# Universal_Board_Side_Mount.net
KiCad netlist of a schematic drawn in EAGLE
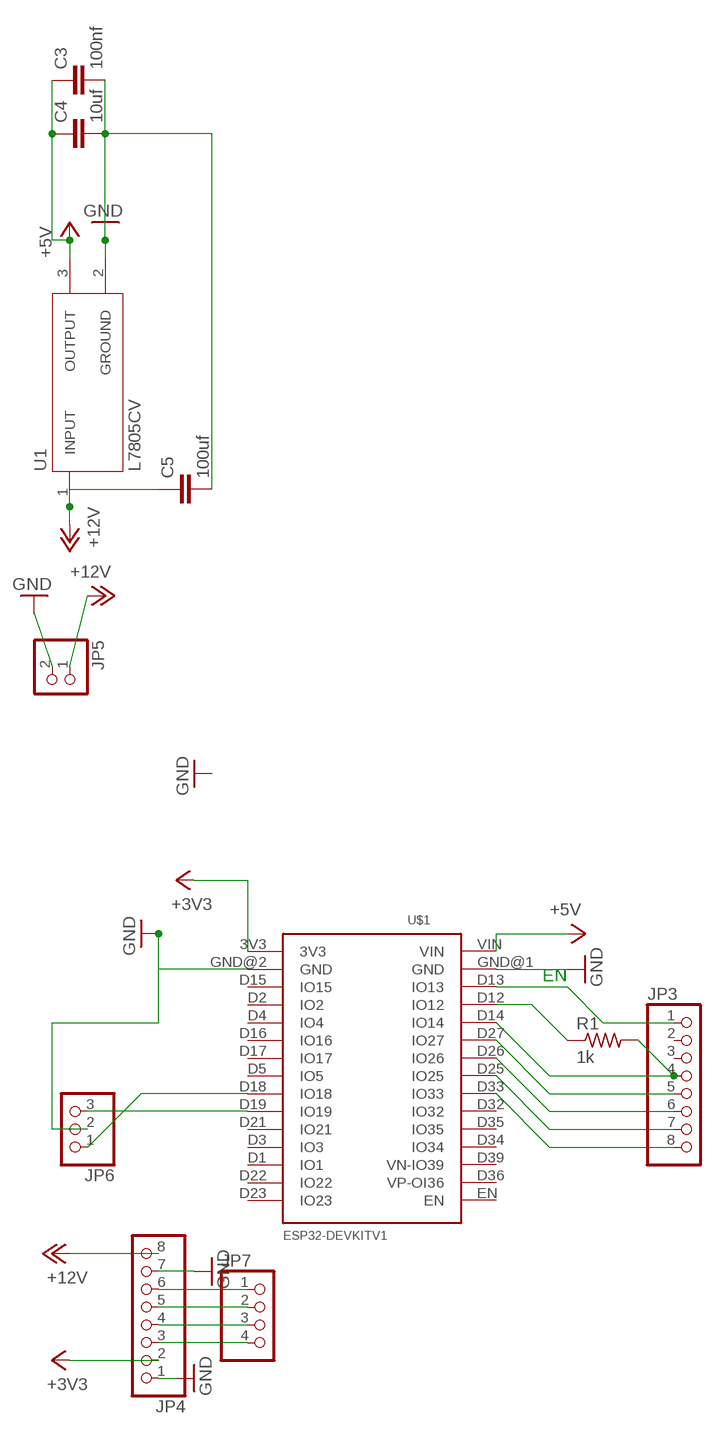
[diagram p0: schematic, sheet 1]

(export (version "E")
  (design (tool "Eeschema 10.0.6"))
  (components
    (comp (ref "C3")
      (value "100nf")
      (footprint "eagle-import:C2.5-3")
      (libsource (lib "eagle-import") (part "C2,5-3"))
    )
    (comp (ref "C4")
      (value "10uf")
      (footprint "eagle-import:C2.5-3")
      (libsource (lib "eagle-import") (part "C2,5-3"))
    )
    (comp (ref "C5")
      (value "100uf")
      (footprint "eagle-import:C2.5-3")
      (libsource (lib "eagle-import") (part "C2,5-3"))
    )
    (comp (ref "JP3")
      (value "PINHD-1X8")
      (footprint "eagle-import:1X08")
      (libsource (lib "eagle-import") (part "PINHD-1X8"))
    )
    (comp (ref "JP4")
      (value "PINHD-1X8")
      (footprint "eagle-import:1X08")
      (libsource (lib "eagle-import") (part "PINHD-1X8"))
    )
    (comp (ref "JP5")
      (value "PINHD-1X2")
      (footprint "eagle-import:1X02")
      (libsource (lib "eagle-import") (part "PINHD-1X2"))
    )
    (comp (ref "JP6")
      (value "PINHD-1X3")
      (footprint "eagle-import:1X03")
      (libsource (lib "eagle-import") (part "PINHD-1X3"))
    )
    (comp (ref "JP7")
      (value "PINHD-1X4")
      (footprint "eagle-import:1X04")
      (libsource (lib "eagle-import") (part "PINHD-1X4"))
    )
    (comp (ref "R1")
      (value "1k")
      (footprint "eagle-import:0204_7")
      (libsource (lib "eagle-import") (part "R-US_0204/7"))
    )
    (comp (ref "U$1")
      (value "ESP32DEVKITV1")
      (footprint "eagle-import:ESP32-DEVKITV1")
      (libsource (lib "eagle-import") (part "ESP32DEVKITV1"))
    )
    (comp (ref "U1")
      (value "L7805CV")
      (footprint "eagle-import:TO255P1040X460X1968-3")
      (fields (field (name "MF") "STMicroelectronics"))
      (libsource (lib "eagle-import") (part "L7805CV"))
    )
  )
  (nets
    (net (code "1") (name "+3V3") (class "Default")
      (node (ref "JP4") (pin "2") (pinfunction "2_2") (pintype "passive"))
      (node (ref "U$1") (pin "3V3") (pinfunction "3V3_3V3") (pintype "bidirectional"))
    )
    (net (code "2") (name "+5V") (class "Default")
      (node (ref "C3") (pin "1") (pinfunction "1_1") (pintype "passive"))
      (node (ref "C4") (pin "1") (pinfunction "1_1") (pintype "passive"))
      (node (ref "U$1") (pin "VIN") (pinfunction "VIN_VIN") (pintype "bidirectional"))
      (node (ref "U1") (pin "3") (pinfunction "OUTPUT_3") (pintype "output"))
    )
    (net (code "3") (name "+12V") (class "Default")
      (node (ref "C5") (pin "1") (pinfunction "1_1") (pintype "passive"))
      (node (ref "JP4") (pin "8") (pinfunction "8_8") (pintype "passive"))
      (node (ref "JP5") (pin "1") (pinfunction "1_1") (pintype "passive"))
      (node (ref "U1") (pin "1") (pinfunction "INPUT_1") (pintype "input"))
    )
    (net (code "4") (name "GND") (class "Default")
      (node (ref "C3") (pin "2") (pinfunction "2_2") (pintype "passive"))
      (node (ref "C4") (pin "2") (pinfunction "2_2") (pintype "passive"))
      (node (ref "C5") (pin "2") (pinfunction "2_2") (pintype "passive"))
      (node (ref "JP4") (pin "1") (pinfunction "1_1") (pintype "passive"))
      (node (ref "JP4") (pin "7") (pinfunction "7_7") (pintype "passive"))
      (node (ref "JP5") (pin "2") (pinfunction "2_2") (pintype "passive"))
      (node (ref "JP6") (pin "2") (pinfunction "2_2") (pintype "passive"))
      (node (ref "U$1") (pin "GND@1") (pinfunction "GND_GND@1") (pintype "bidirectional"))
      (node (ref "U$1") (pin "GND@2") (pinfunction "GND_GND@2") (pintype "bidirectional"))
      (node (ref "U1") (pin "2") (pinfunction "GROUND_2") (pintype "power_in"))
    )
    (net (code "5") (name "Net-(JP4-Pad3)") (class "Default")
      (node (ref "JP4") (pin "3") (pinfunction "3_3") (pintype "passive"))
      (node (ref "JP7") (pin "4") (pinfunction "4_4") (pintype "passive"))
    )
    (net (code "6") (name "Net-(JP4-Pad4)") (class "Default")
      (node (ref "JP4") (pin "4") (pinfunction "4_4") (pintype "passive"))
      (node (ref "JP7") (pin "3") (pinfunction "3_3") (pintype "passive"))
    )
    (net (code "7") (name "Net-(JP4-Pad5)") (class "Default")
      (node (ref "JP4") (pin "5") (pinfunction "5_5") (pintype "passive"))
      (node (ref "JP7") (pin "2") (pinfunction "2_2") (pintype "passive"))
    )
    (net (code "8") (name "Net-(JP4-Pad6)") (class "Default")
      (node (ref "JP4") (pin "6") (pinfunction "6_6") (pintype "passive"))
      (node (ref "JP7") (pin "1") (pinfunction "1_1") (pintype "passive"))
    )
    (net (code "9") (name "Net-(U$1-IO12)") (class "Default")
      (node (ref "R1") (pin "1") (pinfunction "1_1") (pintype "passive"))
      (node (ref "U$1") (pin "D12") (pinfunction "IO12_D12") (pintype "bidirectional"))
    )
    (net (code "10") (name "Net-(U$1-IO13)") (class "Default")
      (node (ref "JP3") (pin "1") (pinfunction "1_1") (pintype "passive"))
      (node (ref "U$1") (pin "D13") (pinfunction "IO13_D13") (pintype "bidirectional"))
    )
    (net (code "11") (name "Net-(U$1-IO14)") (class "Default")
      (node (ref "JP3") (pin "4") (pinfunction "4_4") (pintype "passive"))
      (node (ref "R1") (pin "2") (pinfunction "2_2") (pintype "passive"))
      (node (ref "U$1") (pin "D14") (pinfunction "IO14_D14") (pintype "bidirectional"))
    )
    (net (code "12") (name "Net-(U$1-IO18)") (class "Default")
      (node (ref "JP6") (pin "1") (pinfunction "1_1") (pintype "passive"))
      (node (ref "U$1") (pin "D18") (pinfunction "IO18_D18") (pintype "bidirectional"))
    )
    (net (code "13") (name "Net-(U$1-IO19)") (class "Default")
      (node (ref "JP6") (pin "3") (pinfunction "3_3") (pintype "passive"))
      (node (ref "U$1") (pin "D19") (pinfunction "IO19_D19") (pintype "bidirectional"))
    )
    (net (code "14") (name "Net-(U$1-IO25)") (class "Default")
      (node (ref "JP3") (pin "7") (pinfunction "7_7") (pintype "passive"))
      (node (ref "U$1") (pin "D25") (pinfunction "IO25_D25") (pintype "bidirectional"))
    )
    (net (code "15") (name "Net-(U$1-IO26)") (class "Default")
      (node (ref "JP3") (pin "6") (pinfunction "6_6") (pintype "passive"))
      (node (ref "U$1") (pin "D26") (pinfunction "IO26_D26") (pintype "bidirectional"))
    )
    (net (code "16") (name "Net-(U$1-IO27)") (class "Default")
      (node (ref "JP3") (pin "5") (pinfunction "5_5") (pintype "passive"))
      (node (ref "U$1") (pin "D27") (pinfunction "IO27_D27") (pintype "bidirectional"))
    )
    (net (code "17") (name "Net-(U$1-IO33)") (class "Default")
      (node (ref "JP3") (pin "8") (pinfunction "8_8") (pintype "passive"))
      (node (ref "U$1") (pin "D33") (pinfunction "IO33_D33") (pintype "bidirectional"))
    )
    (net (code "18") (name "unconnected-(JP3-Pad2)") (class "Default")
      (node (ref "JP3") (pin "2") (pinfunction "2_2") (pintype "passive"))
    )
    (net (code "19") (name "unconnected-(JP3-Pad3)") (class "Default")
      (node (ref "JP3") (pin "3") (pinfunction "3_3") (pintype "passive"))
    )
    (net (code "20") (name "unconnected-(U$1-IO1-PadD1)") (class "Default")
      (node (ref "U$1") (pin "D1") (pinfunction "IO1_D1") (pintype "bidirectional"))
    )
    (net (code "21") (name "unconnected-(U$1-IO2-PadD2)") (class "Default")
      (node (ref "U$1") (pin "D2") (pinfunction "IO2_D2") (pintype "bidirectional"))
    )
    (net (code "22") (name "unconnected-(U$1-IO3-PadD3)") (class "Default")
      (node (ref "U$1") (pin "D3") (pinfunction "IO3_D3") (pintype "bidirectional"))
    )
    (net (code "23") (name "unconnected-(U$1-IO4-PadD4)") (class "Default")
      (node (ref "U$1") (pin "D4") (pinfunction "IO4_D4") (pintype "bidirectional"))
    )
    (net (code "24") (name "unconnected-(U$1-IO5-PadD5)") (class "Default")
      (node (ref "U$1") (pin "D5") (pinfunction "IO5_D5") (pintype "bidirectional"))
    )
    (net (code "25") (name "unconnected-(U$1-IO15-PadD15)") (class "Default")
      (node (ref "U$1") (pin "D15") (pinfunction "IO15_D15") (pintype "bidirectional"))
    )
    (net (code "26") (name "unconnected-(U$1-IO16-PadD16)") (class "Default")
      (node (ref "U$1") (pin "D16") (pinfunction "IO16_D16") (pintype "bidirectional"))
    )
    (net (code "27") (name "unconnected-(U$1-IO17-PadD17)") (class "Default")
      (node (ref "U$1") (pin "D17") (pinfunction "IO17_D17") (pintype "bidirectional"))
    )
    (net (code "28") (name "unconnected-(U$1-IO21-PadD21)") (class "Default")
      (node (ref "U$1") (pin "D21") (pinfunction "IO21_D21") (pintype "bidirectional"))
    )
    (net (code "29") (name "unconnected-(U$1-IO22-PadD22)") (class "Default")
      (node (ref "U$1") (pin "D22") (pinfunction "IO22_D22") (pintype "bidirectional"))
    )
    (net (code "30") (name "unconnected-(U$1-IO23-PadD23)") (class "Default")
      (node (ref "U$1") (pin "D23") (pinfunction "IO23_D23") (pintype "bidirectional"))
    )
    (net (code "31") (name "unconnected-(U$1-IO32-PadD32)") (class "Default")
      (node (ref "U$1") (pin "D32") (pinfunction "IO32_D32") (pintype "bidirectional"))
    )
    (net (code "32") (name "unconnected-(U$1-IO34-PadD34)") (class "Default")
      (node (ref "U$1") (pin "D34") (pinfunction "IO34_D34") (pintype "bidirectional"))
    )
    (net (code "33") (name "unconnected-(U$1-IO35-PadD35)") (class "Default")
      (node (ref "U$1") (pin "D35") (pinfunction "IO35_D35") (pintype "bidirectional"))
    )
    (net (code "34") (name "unconnected-(U$1-PadEN)") (class "Default")
      (node (ref "U$1") (pin "EN") (pinfunction "EN_EN") (pintype "bidirectional"))
    )
    (net (code "35") (name "unconnected-(U$1-VN-IO39-PadD39)") (class "Default")
      (node (ref "U$1") (pin "D39") (pinfunction "VN-IO39_D39") (pintype "bidirectional"))
    )
    (net (code "36") (name "unconnected-(U$1-VP-OI36-PadD36)") (class "Default")
      (node (ref "U$1") (pin "D36") (pinfunction "VP-OI36_D36") (pintype "bidirectional"))
    )
  )
)
